# PMOD_to_BeagleWire_Debug_-_CRRYEK.net
KiCad netlist of a schematic drawn in EAGLE
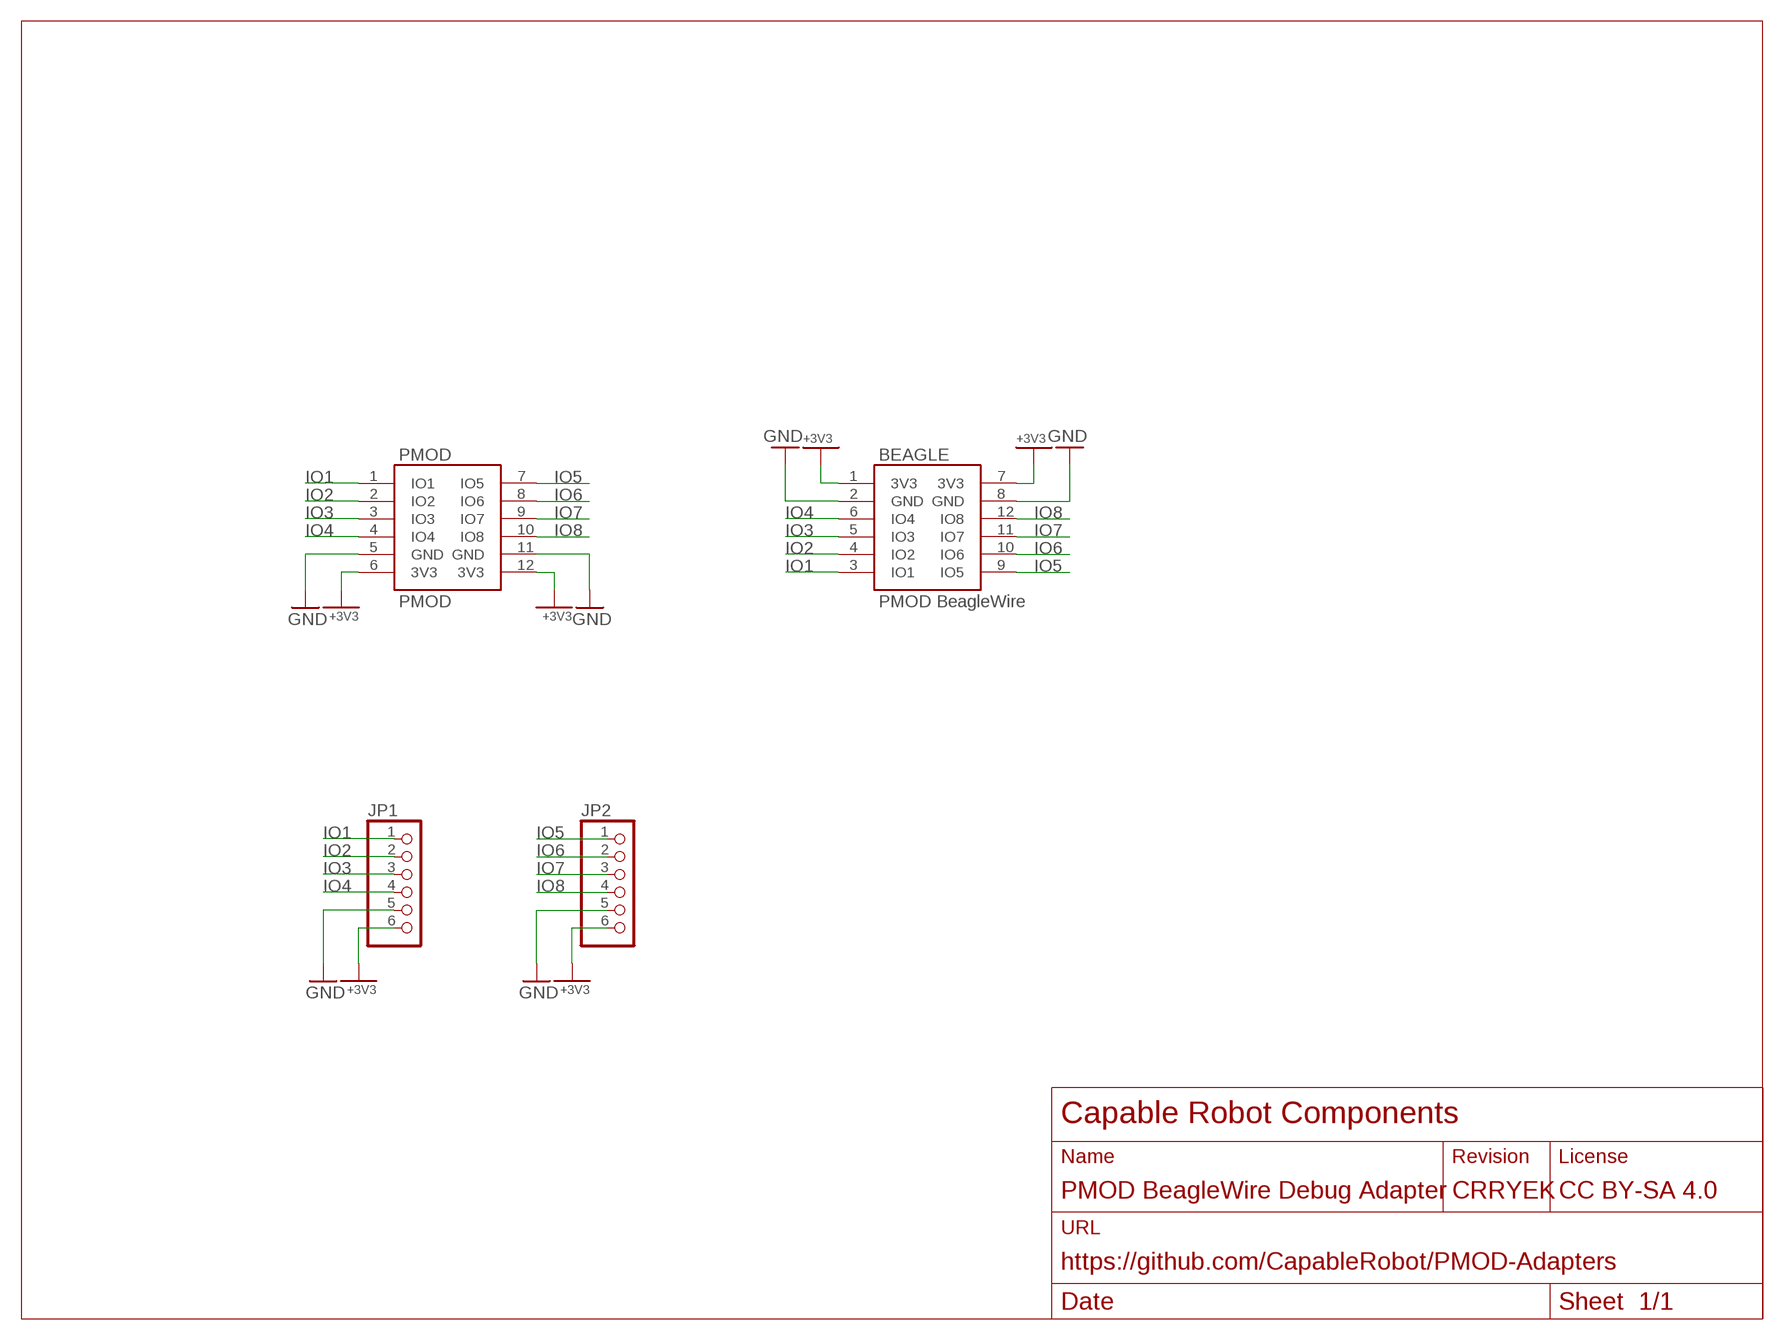
[diagram p0: schematic, sheet 1]

(export (version "E")
  (design (tool "Eeschema 10.0.6"))
  (components
    (comp (ref "BEAGLE")
      (value "PMOD-BEAGLEWIRE")
      (footprint "eagle-import:HDRRA12W64P254_2X6_1524X254X556B")
      (libsource (lib "eagle-import") (part "PMOD-BEAGLEWIRE"))
    )
    (comp (ref "JP1")
      (value "PINHD-1X6")
      (footprint "eagle-import:1X06")
      (libsource (lib "eagle-import") (part "PINHD-1X6"))
    )
    (comp (ref "JP2")
      (value "PINHD-1X6")
      (footprint "eagle-import:1X06")
      (libsource (lib "eagle-import") (part "PINHD-1X6"))
    )
    (comp (ref "PMOD")
      (value "PMOD-HOST")
      (footprint "eagle-import:HDRRAR12W64P254_2X6_1524X736X556B")
      (libsource (lib "eagle-import") (part "PMOD-HOST"))
    )
  )
  (nets
    (net (code "1") (name "+3V3") (class "Default")
      (node (ref "BEAGLE") (pin "1") (pinfunction "3V3_1") (pintype "bidirectional"))
      (node (ref "BEAGLE") (pin "7") (pinfunction "3V3_7") (pintype "bidirectional"))
      (node (ref "JP1") (pin "6") (pinfunction "6_6") (pintype "passive"))
      (node (ref "JP2") (pin "6") (pinfunction "6_6") (pintype "passive"))
      (node (ref "PMOD") (pin "12") (pinfunction "3V3_12") (pintype "bidirectional"))
      (node (ref "PMOD") (pin "6") (pinfunction "3V3_6") (pintype "bidirectional"))
    )
    (net (code "2") (name "/IO1") (class "Default")
      (node (ref "BEAGLE") (pin "3") (pinfunction "IO1_3") (pintype "bidirectional"))
      (node (ref "JP1") (pin "1") (pinfunction "1_1") (pintype "passive"))
      (node (ref "PMOD") (pin "1") (pinfunction "IO1_1") (pintype "bidirectional"))
    )
    (net (code "3") (name "/IO2") (class "Default")
      (node (ref "BEAGLE") (pin "4") (pinfunction "IO2_4") (pintype "bidirectional"))
      (node (ref "JP1") (pin "2") (pinfunction "2_2") (pintype "passive"))
      (node (ref "PMOD") (pin "2") (pinfunction "IO2_2") (pintype "bidirectional"))
    )
    (net (code "4") (name "/IO3") (class "Default")
      (node (ref "BEAGLE") (pin "5") (pinfunction "IO3_5") (pintype "bidirectional"))
      (node (ref "JP1") (pin "3") (pinfunction "3_3") (pintype "passive"))
      (node (ref "PMOD") (pin "3") (pinfunction "IO3_3") (pintype "bidirectional"))
    )
    (net (code "5") (name "/IO4") (class "Default")
      (node (ref "BEAGLE") (pin "6") (pinfunction "IO4_6") (pintype "bidirectional"))
      (node (ref "JP1") (pin "4") (pinfunction "4_4") (pintype "passive"))
      (node (ref "PMOD") (pin "4") (pinfunction "IO4_4") (pintype "bidirectional"))
    )
    (net (code "6") (name "/IO5") (class "Default")
      (node (ref "BEAGLE") (pin "9") (pinfunction "IO5_9") (pintype "bidirectional"))
      (node (ref "JP2") (pin "1") (pinfunction "1_1") (pintype "passive"))
      (node (ref "PMOD") (pin "7") (pinfunction "IO5_7") (pintype "bidirectional"))
    )
    (net (code "7") (name "/IO6") (class "Default")
      (node (ref "BEAGLE") (pin "10") (pinfunction "IO6_10") (pintype "bidirectional"))
      (node (ref "JP2") (pin "2") (pinfunction "2_2") (pintype "passive"))
      (node (ref "PMOD") (pin "8") (pinfunction "IO6_8") (pintype "bidirectional"))
    )
    (net (code "8") (name "/IO7") (class "Default")
      (node (ref "BEAGLE") (pin "11") (pinfunction "IO7_11") (pintype "bidirectional"))
      (node (ref "JP2") (pin "3") (pinfunction "3_3") (pintype "passive"))
      (node (ref "PMOD") (pin "9") (pinfunction "IO7_9") (pintype "bidirectional"))
    )
    (net (code "9") (name "/IO8") (class "Default")
      (node (ref "BEAGLE") (pin "12") (pinfunction "IO8_12") (pintype "bidirectional"))
      (node (ref "JP2") (pin "4") (pinfunction "4_4") (pintype "passive"))
      (node (ref "PMOD") (pin "10") (pinfunction "IO8_10") (pintype "bidirectional"))
    )
    (net (code "10") (name "GND") (class "Default")
      (node (ref "BEAGLE") (pin "2") (pinfunction "GND_2") (pintype "bidirectional"))
      (node (ref "BEAGLE") (pin "8") (pinfunction "GND_8") (pintype "bidirectional"))
      (node (ref "JP1") (pin "5") (pinfunction "5_5") (pintype "passive"))
      (node (ref "JP2") (pin "5") (pinfunction "5_5") (pintype "passive"))
      (node (ref "PMOD") (pin "11") (pinfunction "GND_11") (pintype "bidirectional"))
      (node (ref "PMOD") (pin "5") (pinfunction "GND_5") (pintype "bidirectional"))
    )
  )
)
